# SOLAR_PO.net
KiCad netlist of a schematic drawn in Altium Designer
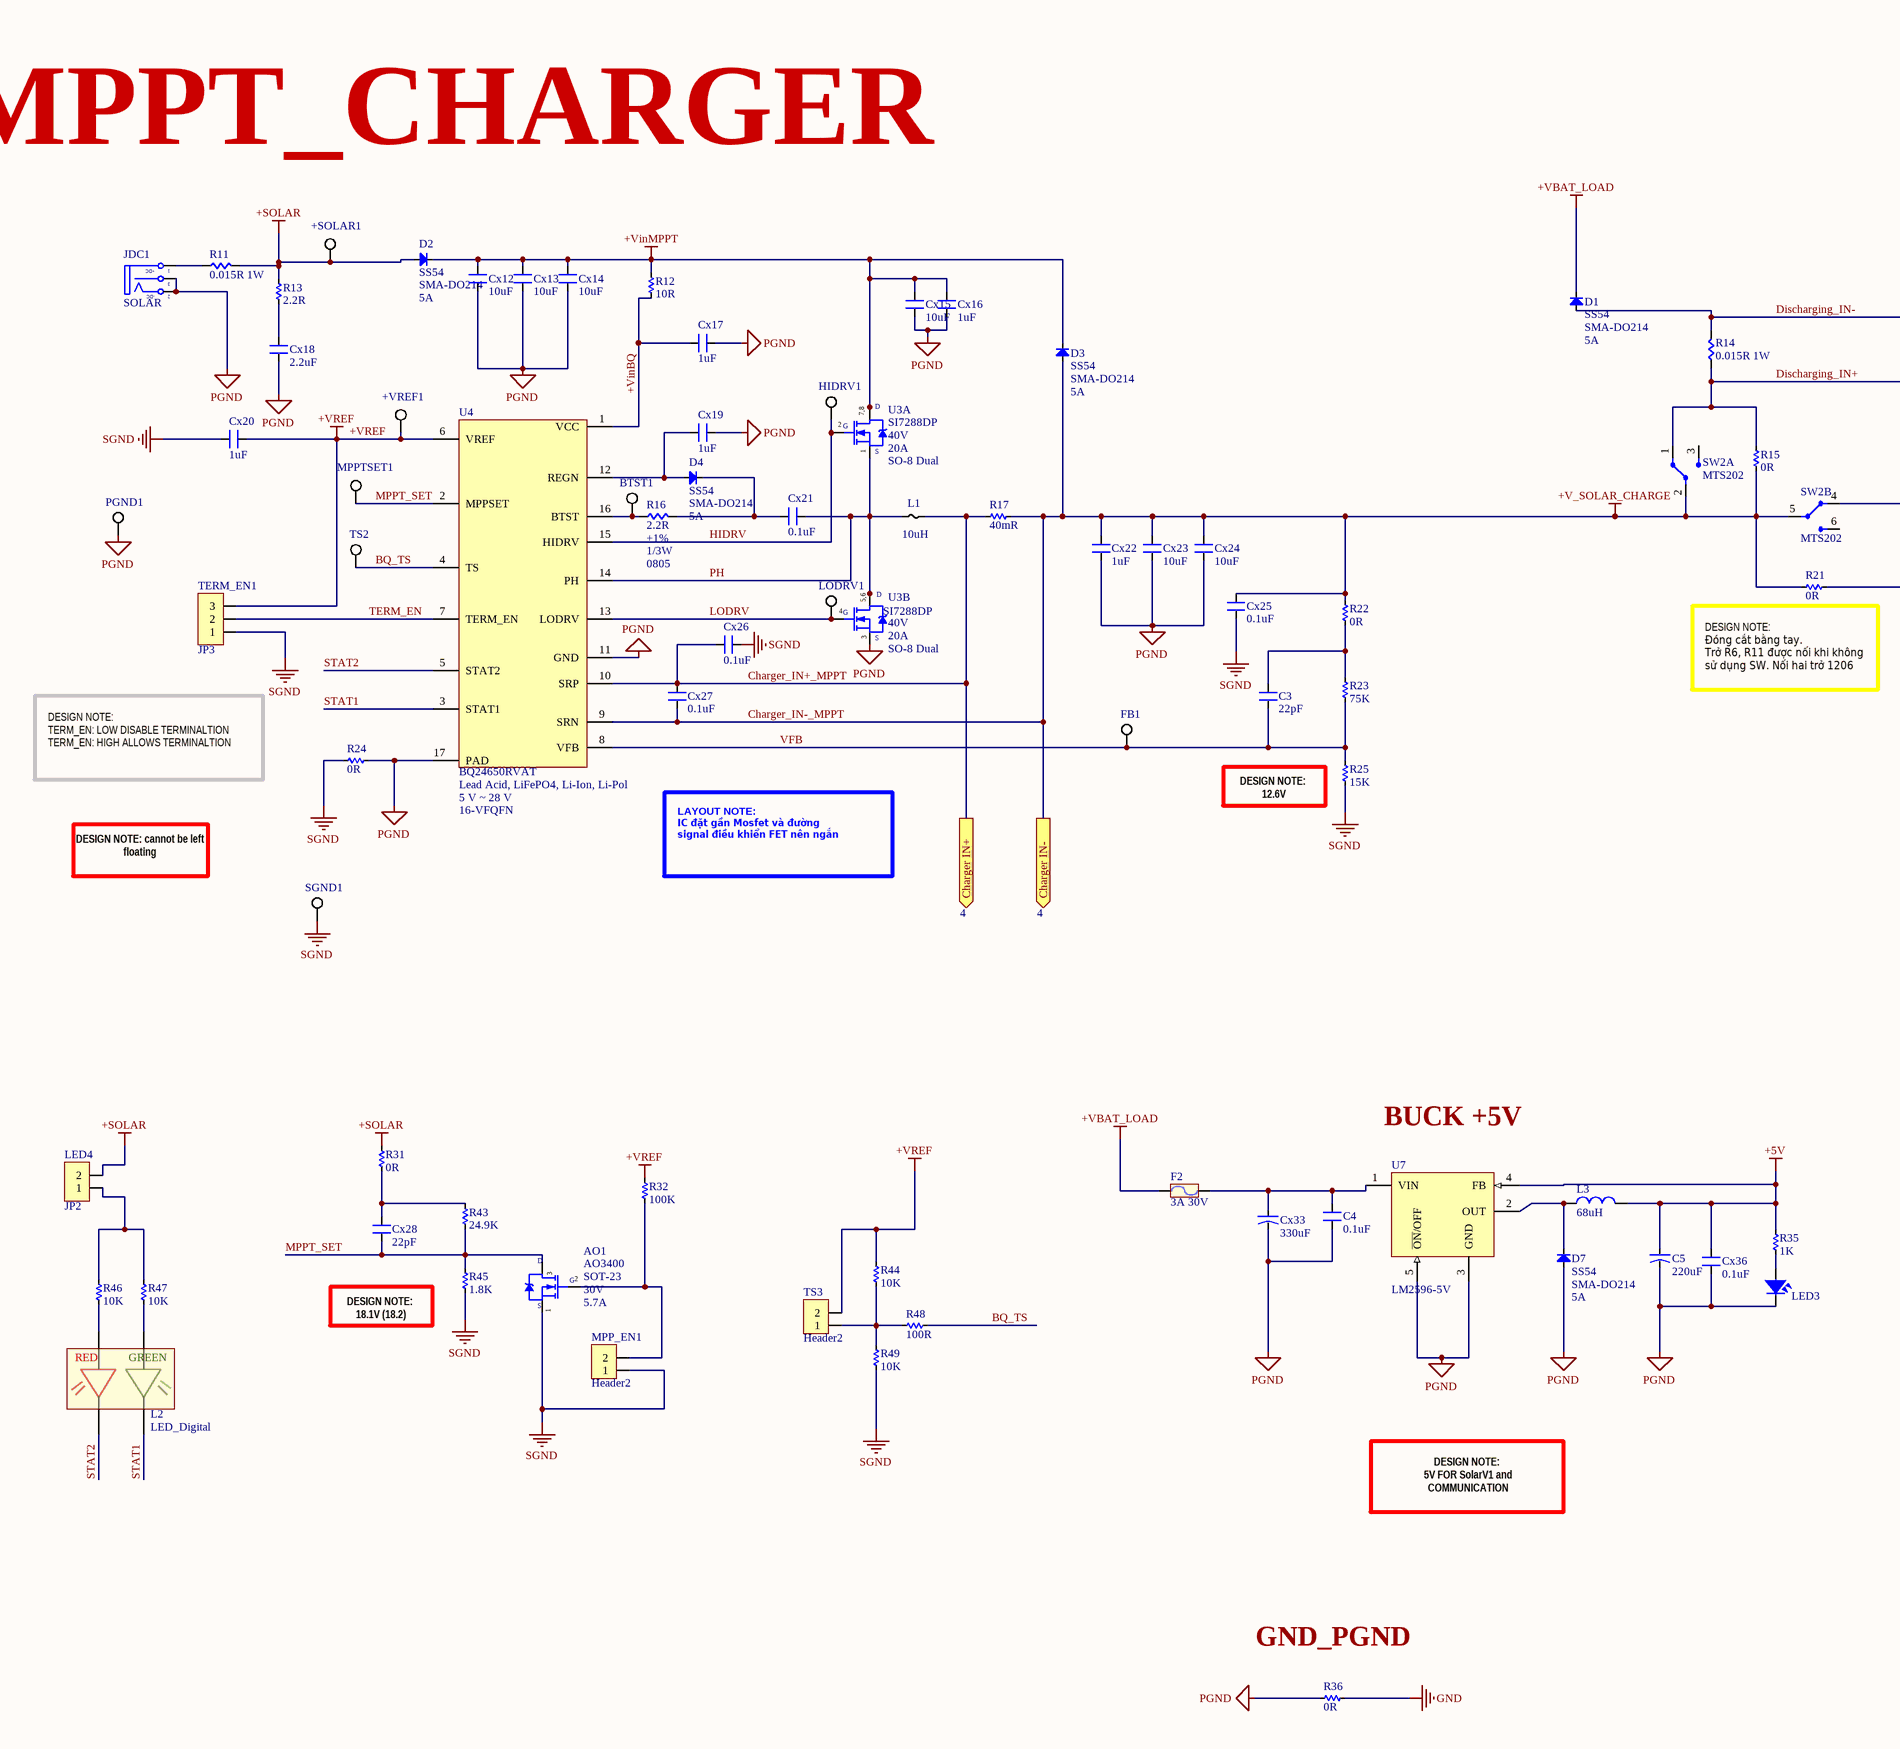
[diagram p0: SOLAR_PO.SchDoc, left]
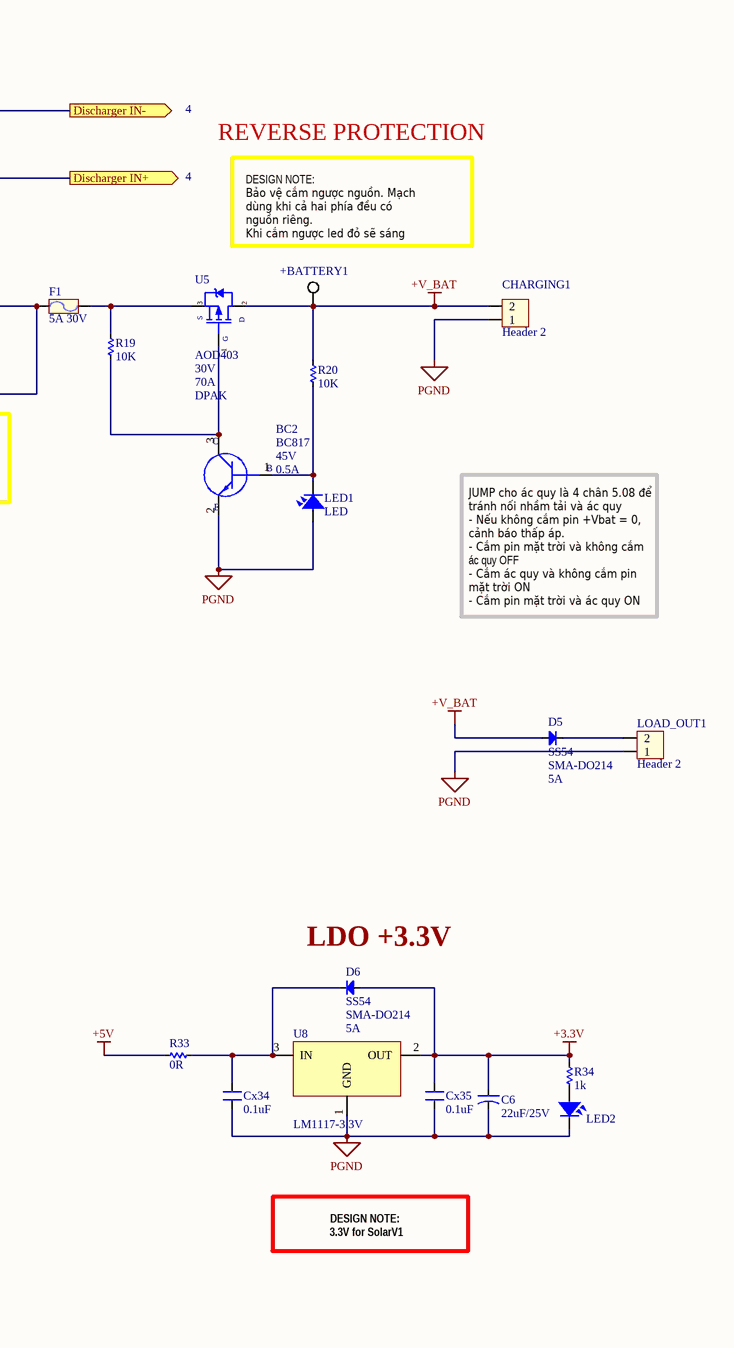
[diagram p1: SOLAR_PO.SchDoc, right]

(export (version "E")
  (design (tool "Eeschema 10.0.6"))
  (components
    (comp (ref "+BATTERY1")
      (value "TP 2x2mm")
      (footprint "TP 2x2mm")
      (libsource (lib "SolarV1") (part "TP 2x2mm"))
    )
    (comp (ref "+SOLAR1")
      (value "TP 2x2mm")
      (footprint "TP 2x2mm")
      (libsource (lib "SolarV1") (part "TP 2x2mm"))
    )
    (comp (ref "+VREF1")
      (value "TP 2x2mm")
      (footprint "TP 2x2mm")
      (libsource (lib "SolarV1") (part "TP 2x2mm"))
    )
    (comp (ref "AO1")
      (value "AO3400")
      (footprint "SOT23-231")
      (description "MOSFET N-CH 30V 5.7A SOT23")
      (fields
        (field (name "MANUFACTURER") "Alpha & Omega Semiconductor")
        (field (name "MANUFACTURER PART NUMBER") "AO3400A")
        (field (name "PACKAGE TYPE") "SOT-23")
        (field (name "DRAIN-SOURCE ON-VOLT") "30V")
        (field (name "CONTINUOUS DRAIN CURRENT") "5.7A")
      )
      (libsource (lib "SolarV1") (part "FET N-CH 4A 30V AO3400A"))
    )
    (comp (ref "BC2")
      (value "BC817")
      (footprint "SOT23-132")
      (description "BC817 Series 45 V 500 mA SMT NPN General Purpose Transistor - SOT-23 VN")
      (fields
        (field (name "MANUFACTURER") "Nexperia")
        (field (name "MANUFACTURER PART NUMBER") "BC817-25,215")
        (field (name "VOLTAGE") "45V")
        (field (name "CURRENT") "0.5A")
      )
      (libsource (lib "SolarV1") (part "TRAN 0.5A 45V BC817-25,215 SOT23 VN"))
    )
    (comp (ref "BTST1")
      (value "TP 2x2mm")
      (footprint "TP 2x2mm")
      (libsource (lib "SolarV1") (part "TP 2x2mm"))
    )
    (comp (ref "C3")
      (value "22pF")
      (footprint "SM-0805")
      (description "Cap Ceramic 22pF 50V C0G 10% Pad SMD 0805 125°C T/R")
      (libsource (lib "SolarV1") (part "CM"))
    )
    (comp (ref "C4")
      (value "0.1uF")
      (footprint "SM-0805")
      (description "Cap SMD")
      (libsource (lib "SolarV1") (part "CM"))
    )
    (comp (ref "C5")
      (value "220uF")
      (footprint "CAP-ALU-SMD-F")
      (description "Polarized Capacitor (Axial)")
      (fields (field (name "PUBLISHER") "Altium Limited"))
      (libsource (lib "SolarV1") (part "CN-ALU-SMD"))
    )
    (comp (ref "C6")
      (value "22uF/25V")
      (footprint "CAP-ALU-SMD-4.5x5x1.4")
      (description "Polarized Capacitor (Axial)")
      (fields (field (name "PUBLISHER") "Altium Limited"))
      (libsource (lib "SolarV1") (part "CN-ALU-SMD"))
    )
    (comp (ref "CHARGING1")
      (value "Header 2")
      (footprint "HED2T")
      (description "Header 2 (Green)")
      (libsource (lib "SolarV1") (part "Hed2"))
    )
    (comp (ref "Cx12") (value "10uF") (footprint "CN-SMD-0805") (libsource (lib "SolarV1") (part "CN")))
    (comp (ref "Cx13") (value "10uF") (footprint "CN-SMD-0805") (libsource (lib "SolarV1") (part "CN")))
    (comp (ref "Cx14") (value "10uF") (footprint "CN-SMD-0805") (libsource (lib "SolarV1") (part "CN")))
    (comp (ref "Cx15") (value "10uF") (footprint "CN-SMD-0805") (libsource (lib "SolarV1") (part "CN")))
    (comp (ref "Cx16") (value "1uF") (footprint "CN-SMD-0805") (libsource (lib "SolarV1") (part "CN")))
    (comp (ref "Cx17") (value "1uF") (footprint "CN-SMD-0805") (libsource (lib "SolarV1") (part "CN")))
    (comp (ref "Cx18") (value "2.2uF") (footprint "CN-SMD-0805") (libsource (lib "SolarV1") (part "CN")))
    (comp (ref "Cx19") (value "1uF") (footprint "CN-SMD-0805") (libsource (lib "SolarV1") (part "CN")))
    (comp (ref "Cx20") (value "1uF") (footprint "CN-SMD-0805") (libsource (lib "SolarV1") (part "CN")))
    (comp (ref "Cx21") (value "0.1uF") (footprint "CN-SMD-0805") (libsource (lib "SolarV1") (part "CN")))
    (comp (ref "Cx22") (value "1uF") (footprint "CN-SMD-0805") (libsource (lib "SolarV1") (part "CN")))
    (comp (ref "Cx23") (value "10uF") (footprint "CN-SMD-0805") (libsource (lib "SolarV1") (part "CN")))
    (comp (ref "Cx24") (value "10uF") (footprint "CN-SMD-0805") (libsource (lib "SolarV1") (part "CN")))
    (comp (ref "Cx25") (value "0.1uF") (footprint "CN-SMD-0805") (libsource (lib "SolarV1") (part "CN")))
    (comp (ref "Cx26") (value "0.1uF") (footprint "CN-SMD-0805") (libsource (lib "SolarV1") (part "CN")))
    (comp (ref "Cx27") (value "0.1uF") (footprint "CN-SMD-0805") (libsource (lib "SolarV1") (part "CN")))
    (comp (ref "Cx28") (value "22pF") (footprint "CN-SMD-0805") (libsource (lib "SolarV1") (part "CN")))
    (comp (ref "Cx33")
      (value "330uF")
      (footprint "CAP SMD ALU SIZE F")
      (description "Polarized Capacitor (Axial)")
      (fields (field (name "PUBLISHER") "Altium Limited"))
      (libsource (lib "SolarV1") (part "CN-ALU-SMD"))
    )
    (comp (ref "Cx34") (value "0.1uF") (footprint "CN-SMD-0805") (libsource (lib "SolarV1") (part "CN")))
    (comp (ref "Cx35") (value "0.1uF") (footprint "CN-SMD-0805") (libsource (lib "SolarV1") (part "CN")))
    (comp (ref "Cx36") (value "0.1uF") (footprint "CN-SMD-0805") (libsource (lib "SolarV1") (part "CN")))
    (comp (ref "D1")
      (value "SS54")
      (footprint "SMA (DO-214AC)")
      (description "SS54 SMA/DO-124AC 5A 40V Schottky Barrier (1N5824) VN")
      (fields (field (name "PACKAGE") "SMA-DO214") (field (name "CURRENT") "5A"))
      (libsource (lib "SolarV1") (part "DIODE 5A 40V SS54  Schottky Diode VN"))
    )
    (comp (ref "D2")
      (value "SS54")
      (footprint "SMA (DO-214AC)")
      (description "SS54 SMA/DO-124AC 5A 40V Schottky Barrier (1N5824) VN")
      (fields (field (name "PACKAGE") "SMA-DO214") (field (name "CURRENT") "5A"))
      (libsource (lib "SolarV1") (part "DIODE 5A 40V SS54  Schottky Diode VN"))
    )
    (comp (ref "D3")
      (value "SS54")
      (footprint "SMA (DO-214AC)")
      (description "SS54 SMA/DO-124AC 5A 40V Schottky Barrier (1N5824) VN")
      (fields (field (name "PACKAGE") "SMA-DO214") (field (name "CURRENT") "5A"))
      (libsource (lib "SolarV1") (part "DIODE 5A 40V SS54  Schottky Diode VN"))
    )
    (comp (ref "D4")
      (value "SS54")
      (footprint "SMA (DO-214AC)")
      (description "SS54 SMA/DO-124AC 5A 40V Schottky Barrier (1N5824) VN")
      (fields (field (name "PACKAGE") "SMA-DO214") (field (name "CURRENT") "5A"))
      (libsource (lib "SolarV1") (part "DIODE 5A 40V SS54  Schottky Diode VN"))
    )
    (comp (ref "D5")
      (value "SS54")
      (footprint "SMA (DO-214AC)")
      (description "SS54 SMA/DO-124AC 5A 40V Schottky Barrier (1N5824) VN")
      (fields (field (name "PACKAGE") "SMA-DO214") (field (name "CURRENT") "5A"))
      (libsource (lib "SolarV1") (part "DIODE 5A 40V SS54  Schottky Diode VN"))
    )
    (comp (ref "D6")
      (value "SS54")
      (footprint "SMA (DO-214AC)")
      (description "SS54 SMA/DO-124AC 5A 40V Schottky Barrier (1N5824) VN")
      (fields (field (name "PACKAGE") "SMA-DO214") (field (name "CURRENT") "5A"))
      (libsource (lib "SolarV1") (part "DIODE 5A 40V SS54  Schottky Diode VN"))
    )
    (comp (ref "D7")
      (value "SS54")
      (footprint "SMA (DO-214AC)")
      (description "SS54 SMA/DO-124AC 5A 40V Schottky Barrier (1N5824) VN")
      (fields (field (name "PACKAGE") "SMA-DO214") (field (name "CURRENT") "5A"))
      (libsource (lib "SolarV1") (part "DIODE 5A 40V SS54  Schottky Diode VN"))
    )
    (comp (ref "F1") (value "5A 30V") (footprint "CN4") (libsource (lib "SolarV1") (part "FUSR 4A 30V DIP")))
    (comp (ref "F2")
      (value "3A 30V")
      (footprint "CN2-G")
      (libsource (lib "SolarV1") (part "FUSE 4A 30V DIP"))
    )
    (comp (ref "FB1") (value "TP 2x2mm") (footprint "TP 2x2mm") (libsource (lib "SolarV1") (part "TP 2x2mm")))
    (comp (ref "HIDRV1")
      (value "TP 2x2mm")
      (footprint "TP 2x2mm")
      (libsource (lib "SolarV1") (part "TP 2x2mm"))
    )
    (comp (ref "JDC1")
      (value "SOLAR")
      (footprint "DC0")
      (description "Jac DC input")
      (libsource (lib "SolarV1") (part "DCIN"))
    )
    (comp (ref "L1")
      (value "10uH")
      (footprint "CDRH104R")
      (description "CDRH104,104R")
      (libsource (lib "SolarV1") (part "inductor"))
    )
    (comp (ref "L2")
      (value "LED_Digital")
      (footprint "LedDigital")
      (description "DBL2")
      (libsource (lib "SolarV1") (part "LED_Digital"))
    )
    (comp (ref "L3")
      (value "68uH")
      (footprint "INDUCTOR SMD 12x12X8.5mm")
      (description "FIXED IND 33UH 3A 64.8 MOHM SMD")
      (fields
        (field (name "MANUFACTURER") "Sumida")
        (field (name "MANUFACTURER PART NUMBER") "CDRH127NP-330MC")
      )
      (libsource (lib "SolarV1") (part "IND 33UH 3A CDRH127NP-330MC"))
    )
    (comp (ref "LED1")
      (value "LED")
      (footprint "LED-5 GRe")
      (description "LED Single colour Green and Red")
      (libsource (lib "SolarV1") (part "LED"))
    )
    (comp (ref "LED2") (value "LED") (footprint "LED-0805-Blue") (libsource (lib "SolarV1") (part "LED SMD")))
    (comp (ref "LED3") (value "LED") (footprint "LED-0805-Red") (libsource (lib "SolarV1") (part "LED SMD")))
    (comp (ref "LED4")
      (value "JP2")
      (footprint "JP2-CLOSED")
      (description "WR-PHD 2.54 mm Angled Socket Header")
      (fields
        (field (name "MANUFACTURER") "Würth Elektronik eiSos GmbH")
        (field (name "PARTNO") "613002143121")
        (field (name "CREATED BY") "Karrer Zheng")
      )
      (libsource (lib "SolarV1") (part "JP2"))
    )
    (comp (ref "LOAD_OUT1")
      (value "Header 2")
      (footprint "HED2T")
      (description "Header 2 (Green)")
      (libsource (lib "SolarV1") (part "Hed2"))
    )
    (comp (ref "LODRV1")
      (value "TP 2x2mm")
      (footprint "TP 2x2mm")
      (libsource (lib "SolarV1") (part "TP 2x2mm"))
    )
    (comp (ref "MPPTSET1")
      (value "TP 2x2mm")
      (footprint "TP 2x2mm")
      (libsource (lib "SolarV1") (part "TP 2x2mm"))
    )
    (comp (ref "MPP_EN1")
      (value "Header2")
      (footprint "JP2-D1T")
      (description "Header IDC, 2 x 1 Pin Vertical 2.54mm Pitch (Non-Boxed, Male)")
      (fields
        (field (name "MANUFACTURER") "Würth Elektronik eiSos GmbH")
        (field (name "PARTNO") "613002143121")
        (field (name "CREATED BY") "Karrer Zheng")
      )
      (libsource (lib "SolarV1") (part "Header2"))
    )
    (comp (ref "PGND1")
      (value "TP 2x2mm")
      (footprint "TP 2x2mm")
      (libsource (lib "SolarV1") (part "TP 2x2mm"))
    )
    (comp (ref "R11")
      (value "0.015R 1W")
      (footprint "RES-SMD-2512")
      (description "RES SMD 15 MOHM 1% 1W 2512")
      (fields
        (field (name "MANUFACTURER") "Vishay Dale")
        (field (name "MANUFACTURER PART NUMBER") "WSL2512R0150FEA")
      )
      (libsource (lib "SolarV1") (part "RES 0.015R 2512 1W 1%"))
    )
    (comp (ref "R12")
      (value "10R")
      (footprint "RES-SMD-0805")
      (description "0805")
      (fields
        (field (name "MANUFACTURER") "Generic Components")
        (field (name "PUBLISHER") "Altium Hobart Technology Centre")
      )
      (libsource (lib "SolarV1") (part "Res-SMD"))
    )
    (comp (ref "R13")
      (value "2.2R")
      (footprint "RES-SMD-2512")
      (description "Resistor")
      (fields
        (field (name "MANUFACTURER") "Generic Components")
        (field (name "PUBLISHER") "Altium Hobart Technology Centre")
      )
      (libsource (lib "SolarV1") (part "Res-SMD"))
    )
    (comp (ref "R14")
      (value "0.015R 1W")
      (footprint "RES-SMD-2512")
      (description "RES SMD 15 MOHM 1% 1W 2512")
      (fields
        (field (name "MANUFACTURER") "Vishay Dale")
        (field (name "MANUFACTURER PART NUMBER") "WSL2512R0150FEA")
      )
      (libsource (lib "SolarV1") (part "RES 0.015R 2512 1W 1%"))
    )
    (comp (ref "R15")
      (value "0R")
      (footprint "RES-SMD-1206")
      (description "Resistor")
      (fields
        (field (name "MANUFACTURER") "Generic Components")
        (field (name "PUBLISHER") "Altium Hobart Technology Centre")
      )
      (libsource (lib "SolarV1") (part "Res-SMD"))
    )
    (comp (ref "R16")
      (value "2.2R")
      (footprint "RES-SMD-0805")
      (description "RES SMD 2.2 OHM 1% 1/3W 0805 VN")
      (fields
        (field (name "MANUFACTURER") "Susumu")
        (field (name "MANUFACTURER PART NUMBER") "RL1220S-2R2-F")
        (field (name "TOLERANCE") "±1%")
        (field (name "POWER (WATTS)") "1/3W")
        (field (name "SUPPLIER DEVICE PACKAGE") "0805")
      )
      (libsource (lib "SolarV1") (part "RES 2.2R 1% 0805 RL1220S-2R2-F VN"))
    )
    (comp (ref "R17")
      (value "40mR")
      (footprint "RES-SMD-2512")
      (description "Resistor")
      (fields
        (field (name "MANUFACTURER") "Generic Components")
        (field (name "PUBLISHER") "Altium Hobart Technology Centre")
      )
      (libsource (lib "SolarV1") (part "Res-SMD"))
    )
    (comp (ref "R19")
      (value "10K")
      (footprint "RES-SMD-0805")
      (description "Resistor")
      (fields
        (field (name "MANUFACTURER") "Generic Components")
        (field (name "PUBLISHER") "Altium Hobart Technology Centre")
      )
      (libsource (lib "SolarV1") (part "Res-SMD"))
    )
    (comp (ref "R20")
      (value "10K")
      (footprint "RES-SMD-0805")
      (description "Resistor")
      (fields
        (field (name "MANUFACTURER") "Generic Components")
        (field (name "PUBLISHER") "Altium Hobart Technology Centre")
      )
      (libsource (lib "SolarV1") (part "Res-SMD"))
    )
    (comp (ref "R21")
      (value "0R")
      (footprint "RES-SMD-1206")
      (description "Resistor")
      (fields
        (field (name "MANUFACTURER") "Generic Components")
        (field (name "PUBLISHER") "Altium Hobart Technology Centre")
      )
      (libsource (lib "SolarV1") (part "Res-SMD"))
    )
    (comp (ref "R22")
      (value "0R")
      (footprint "RES-SMD-0805")
      (description "Resistor")
      (fields
        (field (name "MANUFACTURER") "Generic Components")
        (field (name "PUBLISHER") "Altium Hobart Technology Centre")
      )
      (libsource (lib "SolarV1") (part "Res-SMD"))
    )
    (comp (ref "R23")
      (value "75K")
      (footprint "RES-SMD-0805")
      (description "Resistor")
      (fields
        (field (name "MANUFACTURER") "Generic Components")
        (field (name "PUBLISHER") "Altium Hobart Technology Centre")
      )
      (libsource (lib "SolarV1") (part "Res-SMD"))
    )
    (comp (ref "R24")
      (value "0R")
      (footprint "RES-SMD-0805")
      (description "Resistor")
      (fields
        (field (name "MANUFACTURER") "Generic Components")
        (field (name "PUBLISHER") "Altium Hobart Technology Centre")
      )
      (libsource (lib "SolarV1") (part "Res-SMD"))
    )
    (comp (ref "R25")
      (value "15K")
      (footprint "RES-SMD-0805")
      (description "Resistor")
      (fields
        (field (name "MANUFACTURER") "Generic Components")
        (field (name "PUBLISHER") "Altium Hobart Technology Centre")
      )
      (libsource (lib "SolarV1") (part "Res-SMD"))
    )
    (comp (ref "R31")
      (value "0R")
      (footprint "RES-SMD-0805")
      (description "Resistor")
      (fields
        (field (name "MANUFACTURER") "Generic Components")
        (field (name "PUBLISHER") "Altium Hobart Technology Centre")
      )
      (libsource (lib "SolarV1") (part "Res-SMD"))
    )
    (comp (ref "R32")
      (value "100K")
      (footprint "RES-SMD-0805")
      (description "Resistor")
      (fields
        (field (name "MANUFACTURER") "Generic Components")
        (field (name "PUBLISHER") "Altium Hobart Technology Centre")
      )
      (libsource (lib "SolarV1") (part "Res-SMD"))
    )
    (comp (ref "R33")
      (value "0R")
      (footprint "RES-SMD-0805")
      (description "Resistor")
      (fields
        (field (name "MANUFACTURER") "Generic Components")
        (field (name "PUBLISHER") "Altium Hobart Technology Centre")
      )
      (libsource (lib "SolarV1") (part "Res-SMD"))
    )
    (comp (ref "R34")
      (value "1k")
      (footprint "RES-SMD-0805")
      (description "Resistor")
      (fields
        (field (name "MANUFACTURER") "Generic Components")
        (field (name "PUBLISHER") "Altium Hobart Technology Centre")
      )
      (libsource (lib "SolarV1") (part "Res-SMD"))
    )
    (comp (ref "R35")
      (value "1K")
      (footprint "RES-SMD-0805")
      (description "Resistor")
      (fields
        (field (name "MANUFACTURER") "Generic Components")
        (field (name "PUBLISHER") "Altium Hobart Technology Centre")
      )
      (libsource (lib "SolarV1") (part "Res-SMD"))
    )
    (comp (ref "R36")
      (value "0R")
      (footprint "RES-SMD-0805")
      (description "Resistor")
      (fields
        (field (name "MANUFACTURER") "Generic Components")
        (field (name "PUBLISHER") "Altium Hobart Technology Centre")
      )
      (libsource (lib "SolarV1") (part "Res-SMD"))
    )
    (comp (ref "R43")
      (value "24.9K")
      (footprint "RES-SMD-0805")
      (description "Resistor")
      (fields
        (field (name "MANUFACTURER") "Generic Components")
        (field (name "PUBLISHER") "Altium Hobart Technology Centre")
      )
      (libsource (lib "SolarV1") (part "Res-SMD"))
    )
    (comp (ref "R44")
      (value "10K")
      (footprint "RES-SMD-0805")
      (description "Resistor")
      (fields
        (field (name "MANUFACTURER") "Generic Components")
        (field (name "PUBLISHER") "Altium Hobart Technology Centre")
      )
      (libsource (lib "SolarV1") (part "Res-SMD"))
    )
    (comp (ref "R45")
      (value "1.8K")
      (footprint "RES-SMD-0805")
      (description "Resistor")
      (fields
        (field (name "MANUFACTURER") "Generic Components")
        (field (name "PUBLISHER") "Altium Hobart Technology Centre")
      )
      (libsource (lib "SolarV1") (part "Res-SMD"))
    )
    (comp (ref "R46")
      (value "10K")
      (footprint "RES-SMD-0805")
      (description "Resistor")
      (fields
        (field (name "MANUFACTURER") "Generic Components")
        (field (name "PUBLISHER") "Altium Hobart Technology Centre")
      )
      (libsource (lib "SolarV1") (part "Res-SMD"))
    )
    (comp (ref "R47")
      (value "10K")
      (footprint "RES-SMD-0805")
      (description "Resistor")
      (fields
        (field (name "MANUFACTURER") "Generic Components")
        (field (name "PUBLISHER") "Altium Hobart Technology Centre")
      )
      (libsource (lib "SolarV1") (part "Res-SMD"))
    )
    (comp (ref "R48")
      (value "100R")
      (footprint "RES-SMD-0805")
      (description "Resistor")
      (fields
        (field (name "MANUFACTURER") "Generic Components")
        (field (name "PUBLISHER") "Altium Hobart Technology Centre")
      )
      (libsource (lib "SolarV1") (part "Res-SMD"))
    )
    (comp (ref "R49")
      (value "10K")
      (footprint "RES-SMD-0805")
      (description "Resistor")
      (fields
        (field (name "MANUFACTURER") "Generic Components")
        (field (name "PUBLISHER") "Altium Hobart Technology Centre")
      )
      (libsource (lib "SolarV1") (part "Res-SMD"))
    )
    (comp (ref "SGND1")
      (value "TP 2x2mm")
      (footprint "TP 2x2mm")
      (libsource (lib "SolarV1") (part "TP 2x2mm"))
    )
    (comp (ref "SW2") (value "MTS202") (footprint "MTS-20X") (libsource (lib "") (part "SW MTS202 ON-ON_1")))
    (comp (ref "TERM_EN1")
      (value "JP3")
      (footprint "JP3-D1T")
      (description "WR-PHD 2.54 mm Angled Socket Header")
      (fields
        (field (name "MANUFACTURER") "Würth Elektronik eiSos GmbH")
        (field (name "PARTNO") "613003143121")
        (field (name "CREATED BY") "Karrer Zheng")
      )
      (libsource (lib "SolarV1") (part "JP3"))
    )
    (comp (ref "TS2") (value "TP 2x2mm") (footprint "TP 2x2mm") (libsource (lib "SolarV1") (part "TP 2x2mm")))
    (comp (ref "TS3")
      (value "Header2")
      (footprint "JP2-D1T")
      (description "Header IDC, 2 x 1 Pin Vertical 2.54mm Pitch (Non-Boxed, Male)")
      (fields
        (field (name "MANUFACTURER") "Würth Elektronik eiSos GmbH")
        (field (name "PARTNO") "613002143121")
        (field (name "CREATED BY") "Karrer Zheng")
      )
      (libsource (lib "SolarV1") (part "Header2"))
    )
    (comp (ref "U3")
      (value "SI7288DP")
      (footprint "SO-8 PowerPAK")
      (description "MOSFET 2N-CH 40V 20A PPAK SO-8")
      (fields
        (field (name "MANUFACTURER") "Vishay Siliconix")
        (field (name "MANUFACTURER PART NUMBER") "SI7288DP-T1-GE3")
        (field (name "DRAIN TO SOURCE VOLTAGE (VDSS)") "40V")
        (field (name "CURRENT - CONTINUOUS DRAIN (ID) @ 25°C") "20A")
        (field (name "PACKAGE / CASE") "SO-8 Dual")
      )
      (libsource (lib "SolarV1") (part "FET SI7288DP-T1-GE3"))
    )
    (comp (ref "U4")
      (value "BQ24650RVAT")
      (footprint "VFQFN-16-EP")
      (description "TEXAS INSTRUMENTS         BQ24650RVAT            IC, BATT CHARGER, LI-ION, 10A, VQFN-16")
      (fields
        (field (name "MANUFACTURER") "Texas Instruments")
        (field (name "BATTERY CHEMISTRY") "Lead Acid, LiFePO4, Li-Ion, Li-Pol")
        (field (name "VOLTAGE - SUPPLY") "5 V ~ 28 V")
        (field (name "PACKAGE / CASE") "16-VFQFN")
      )
      (libsource (lib "SolarV1") (part "BQ24650RVAT"))
    )
    (comp (ref "U5")
      (value "AOD403")
      (footprint "TO-252 DPAK")
      (description "Trans MOSFET P-CH 30V 70A 3-Pin(2+Tab) DPAK VN")
      (fields
        (field (name "MANUFACTURER") "Alpha & Omega Semiconductor")
        (field (name "DRAIN-SOURCE ON-VOLT") "30V")
        (field (name "CONTINUOUS DRAIN CURRENT") "70A")
        (field (name "PACKAGE TYPE") "DPAK")
      )
      (libsource (lib "SolarV1") (part "FET P-CH 70A 40V AOD403 VN"))
    )
    (comp (ref "U7")
      (value "LM2596-5V")
      (footprint "TO263")
      (description "IC REG BUCK 5V 3A TO263-5")
      (fields
        (field (name "MANUFACTURER") "Texas Instruments")
        (field (name "MANUFACTURER PART NUMBER") "LM2596SX-5.0/NOPB")
      )
      (libsource (lib "SolarV1") (part "BUCK 5V LM2596SX-5.0/NOPB"))
    )
    (comp (ref "U8")
      (value "LM1117-3.3V")
      (footprint "SOT223")
      (description "800mA Low-Dropout Linear Regulator")
      (fields (field (name "CREATOR") "Nguyen Ba Bien"))
      (libsource (lib "SolarV1") (part "LM1117"))
    )
  )
  (nets
    (net (code "1") (name "+3.3V") (class "Default")
      (node (ref "C6") (pin "1") (pinfunction "1_1") (pintype "passive"))
      (node (ref "Cx35") (pin "2") (pinfunction "2_2") (pintype "passive"))
      (node (ref "D6") (pin "1") (pinfunction "A_1") (pintype "passive"))
      (node (ref "R34") (pin "1") (pinfunction "1_1") (pintype "passive"))
      (node (ref "U8") (pin "2") (pinfunction "OUT_2") (pintype "passive"))
    )
    (net (code "2") (name "+5V") (class "Default")
      (node (ref "C5") (pin "1") (pinfunction "1_1") (pintype "passive"))
      (node (ref "Cx36") (pin "2") (pinfunction "2_2") (pintype "passive"))
      (node (ref "L3") (pin "2") (pinfunction "2_2") (pintype "passive"))
      (node (ref "R33") (pin "2") (pinfunction "2_2") (pintype "passive"))
      (node (ref "R35") (pin "1") (pinfunction "1_1") (pintype "passive"))
      (node (ref "U7") (pin "4") (pinfunction "FB_4") (pintype "input"))
    )
    (net (code "3") (name "+SOLAR") (class "Default")
      (node (ref "+SOLAR1") (pin "3") (pinfunction "3_3") (pintype "passive"))
      (node (ref "D2") (pin "1") (pinfunction "A_1") (pintype "passive"))
      (node (ref "LED4") (pin "2") (pinfunction "2_2") (pintype "passive"))
      (node (ref "R11") (pin "2") (pinfunction "2_2") (pintype "passive"))
      (node (ref "R13") (pin "1") (pinfunction "1_1") (pintype "passive"))
      (node (ref "R31") (pin "1") (pinfunction "1_1") (pintype "passive"))
    )
    (net (code "4") (name "+VBAT_LOAD") (class "Default")
      (node (ref "D1") (pin "2") (pinfunction "K_2") (pintype "passive"))
      (node (ref "F2") (pin "1") (pinfunction "1_1") (pintype "passive"))
    )
    (net (code "5") (name "+VREF") (class "Default")
      (node (ref "+VREF1") (pin "3") (pinfunction "3_3") (pintype "passive"))
      (node (ref "Cx20") (pin "1") (pinfunction "1_1") (pintype "passive"))
      (node (ref "R32") (pin "1") (pinfunction "1_1") (pintype "passive"))
      (node (ref "R44") (pin "1") (pinfunction "1_1") (pintype "passive"))
      (node (ref "TERM_EN1") (pin "3") (pinfunction "3_3") (pintype "passive"))
      (node (ref "TS3") (pin "2") (pinfunction "2_2") (pintype "passive"))
      (node (ref "U4") (pin "6") (pinfunction "VREF_6") (pintype "passive"))
    )
    (net (code "6") (name "+V_BAT") (class "Default")
      (node (ref "+BATTERY1") (pin "3") (pinfunction "3_3") (pintype "passive"))
      (node (ref "CHARGING1") (pin "2") (pinfunction "2_2") (pintype "passive"))
      (node (ref "D5") (pin "1") (pinfunction "A_1") (pintype "passive"))
      (node (ref "R20") (pin "2") (pinfunction "2_2") (pintype "passive"))
      (node (ref "U5") (pin "2") (pinfunction "D_2") (pintype "passive"))
    )
    (net (code "7") (name "+V_SOLAR_CHARGE") (class "Default")
      (node (ref "Cx22") (pin "1") (pinfunction "1_1") (pintype "passive"))
      (node (ref "Cx23") (pin "1") (pinfunction "1_1") (pintype "passive"))
      (node (ref "Cx24") (pin "2") (pinfunction "2_2") (pintype "passive"))
      (node (ref "Cx25") (pin "1") (pinfunction "1_1") (pintype "passive"))
      (node (ref "Cx27") (pin "2") (pinfunction "2_2") (pintype "passive"))
      (node (ref "D3") (pin "1") (pinfunction "A_1") (pintype "passive"))
      (node (ref "R15") (pin "1") (pinfunction "1_1") (pintype "passive"))
      (node (ref "R17") (pin "1") (pinfunction "1_1") (pintype "passive"))
      (node (ref "R21") (pin "1") (pinfunction "1_1") (pintype "passive"))
      (node (ref "R22") (pin "1") (pinfunction "1_1") (pintype "passive"))
      (node (ref "SW2") (pin "2") (pintype "passive"))
      (node (ref "SW2") (pin "5") (pintype "passive"))
      (node (ref "U4") (pin "9") (pinfunction "SRN_9") (pintype "passive"))
    )
    (net (code "8") (name "+VinMPPT") (class "Default")
      (node (ref "Cx12") (pin "2") (pinfunction "2_2") (pintype "passive"))
      (node (ref "Cx13") (pin "2") (pinfunction "2_2") (pintype "passive"))
      (node (ref "Cx14") (pin "2") (pinfunction "2_2") (pintype "passive"))
      (node (ref "Cx15") (pin "2") (pinfunction "2_2") (pintype "passive"))
      (node (ref "Cx16") (pin "1") (pinfunction "1_1") (pintype "passive"))
      (node (ref "D2") (pin "2") (pinfunction "K_2") (pintype "passive"))
      (node (ref "D3") (pin "2") (pinfunction "K_2") (pintype "passive"))
      (node (ref "R12") (pin "1") (pinfunction "1_1") (pintype "passive"))
      (node (ref "U3") (pin "7") (pinfunction "D_7") (pintype "passive"))
      (node (ref "U3") (pin "8") (pinfunction "D_8") (pintype "passive"))
    )
    (net (code "9") (name "/+VinBQ") (class "Default")
      (node (ref "Cx17") (pin "2") (pinfunction "2_2") (pintype "passive"))
      (node (ref "R12") (pin "2") (pinfunction "2_2") (pintype "passive"))
      (node (ref "U4") (pin "1") (pinfunction "VCC_1") (pintype "passive"))
    )
    (net (code "10") (name "/BQ_TS") (class "Default")
      (node (ref "R48") (pin "2") (pinfunction "2_2") (pintype "passive"))
      (node (ref "TS2") (pin "3") (pinfunction "3_3") (pintype "passive"))
      (node (ref "U4") (pin "4") (pinfunction "TS_4") (pintype "passive"))
    )
    (net (code "11") (name "/Charger_IN+_MPPT") (class "Default")
      (node (ref "Cx26") (pin "2") (pinfunction "2_2") (pintype "passive"))
      (node (ref "Cx27") (pin "1") (pinfunction "1_1") (pintype "passive"))
      (node (ref "L1") (pin "2") (pinfunction "2_2") (pintype "passive"))
      (node (ref "R17") (pin "2") (pinfunction "2_2") (pintype "passive"))
      (node (ref "U4") (pin "10") (pinfunction "SRP_10") (pintype "passive"))
    )
    (net (code "12") (name "/Discharging_IN+") (class "Default")
      (node (ref "R14") (pin "1") (pinfunction "1_1") (pintype "passive"))
      (node (ref "R15") (pin "2") (pinfunction "2_2") (pintype "passive"))
      (node (ref "SW2") (pin "1") (pintype "passive"))
    )
    (net (code "13") (name "/Discharging_IN-") (class "Default")
      (node (ref "D1") (pin "1") (pinfunction "A_1") (pintype "passive"))
      (node (ref "R14") (pin "2") (pinfunction "2_2") (pintype "passive"))
    )
    (net (code "14") (name "/HIDRV") (class "Default")
      (node (ref "HIDRV1") (pin "3") (pinfunction "3_3") (pintype "passive"))
      (node (ref "U3") (pin "2") (pinfunction "G_2") (pintype "passive"))
      (node (ref "U4") (pin "15") (pinfunction "HIDRV_15") (pintype "passive"))
    )
    (net (code "15") (name "/LODRV") (class "Default")
      (node (ref "LODRV1") (pin "3") (pinfunction "3_3") (pintype "passive"))
      (node (ref "U3") (pin "4") (pinfunction "G_4") (pintype "passive"))
      (node (ref "U4") (pin "13") (pinfunction "LODRV_13") (pintype "passive"))
    )
    (net (code "16") (name "/MPPT_SET") (class "Default")
      (node (ref "AO1") (pin "3") (pinfunction "D_3") (pintype "passive"))
      (node (ref "Cx28") (pin "2") (pinfunction "2_2") (pintype "passive"))
      (node (ref "MPPTSET1") (pin "3") (pinfunction "3_3") (pintype "passive"))
      (node (ref "R43") (pin "2") (pinfunction "2_2") (pintype "passive"))
      (node (ref "R45") (pin "1") (pinfunction "1_1") (pintype "passive"))
      (node (ref "U4") (pin "2") (pinfunction "MPPSET_2") (pintype "passive"))
    )
    (net (code "17") (name "/PH") (class "Default")
      (node (ref "Cx21") (pin "1") (pinfunction "1_1") (pintype "passive"))
      (node (ref "L1") (pin "1") (pinfunction "1_1") (pintype "passive"))
      (node (ref "U3") (pin "1") (pinfunction "S_1") (pintype "passive"))
      (node (ref "U3") (pin "5") (pinfunction "D_5") (pintype "passive"))
      (node (ref "U3") (pin "6") (pinfunction "D_6") (pintype "passive"))
      (node (ref "U4") (pin "14") (pinfunction "PH_14") (pintype "passive"))
    )
    (net (code "18") (name "/STAT1") (class "Default")
      (node (ref "L2") (pin "4") (pinfunction "4_4") (pintype "passive"))
      (node (ref "U4") (pin "3") (pinfunction "STAT1_3") (pintype "passive"))
    )
    (net (code "19") (name "/STAT2") (class "Default")
      (node (ref "L2") (pin "2") (pinfunction "2_2") (pintype "passive"))
      (node (ref "U4") (pin "5") (pinfunction "STAT2_5") (pintype "passive"))
    )
    (net (code "20") (name "/TERM_EN") (class "Default")
      (node (ref "TERM_EN1") (pin "2") (pinfunction "2_2") (pintype "passive"))
      (node (ref "U4") (pin "7") (pinfunction "TERM_EN_7") (pintype "passive"))
    )
    (net (code "21") (name "/VFB") (class "Default")
      (node (ref "C3") (pin "1") (pinfunction "1_1") (pintype "passive"))
      (node (ref "FB1") (pin "3") (pinfunction "3_3") (pintype "passive"))
      (node (ref "R23") (pin "2") (pinfunction "2_2") (pintype "passive"))
      (node (ref "R25") (pin "1") (pinfunction "1_1") (pintype "passive"))
      (node (ref "U4") (pin "8") (pinfunction "VFB_8") (pintype "passive"))
    )
    (net (code "22") (name "GND") (class "Default")
      (node (ref "R36") (pin "1") (pinfunction "1_1") (pintype "passive"))
    )
    (net (code "23") (name "Net-(AO1-G)") (class "Default")
      (node (ref "AO1") (pin "2") (pinfunction "G_2") (pintype "passive"))
      (node (ref "MPP_EN1") (pin "2") (pinfunction "2_2") (pintype "passive"))
      (node (ref "R32") (pin "2") (pinfunction "2_2") (pintype "passive"))
    )
    (net (code "24") (name "Net-(BC2-B)") (class "Default")
      (node (ref "BC2") (pin "1") (pinfunction "B_1") (pintype "passive"))
      (node (ref "LED1") (pin "2") (pinfunction "2_2") (pintype "passive"))
      (node (ref "R20") (pin "1") (pinfunction "1_1") (pintype "passive"))
    )
    (net (code "25") (name "Net-(BC2-C)") (class "Default")
      (node (ref "BC2") (pin "3") (pinfunction "C_3") (pintype "passive"))
      (node (ref "R19") (pin "1") (pinfunction "1_1") (pintype "passive"))
      (node (ref "U5") (pin "1") (pinfunction "G_1") (pintype "passive"))
    )
    (net (code "26") (name "Net-(C3-Pad2)") (class "Default")
      (node (ref "C3") (pin "2") (pinfunction "2_2") (pintype "passive"))
      (node (ref "R22") (pin "2") (pinfunction "2_2") (pintype "passive"))
      (node (ref "R23") (pin "1") (pinfunction "1_1") (pintype "passive"))
    )
    (net (code "27") (name "Net-(Cx18-Pad2)") (class "Default")
      (node (ref "Cx18") (pin "2") (pinfunction "2_2") (pintype "passive"))
      (node (ref "R13") (pin "2") (pinfunction "2_2") (pintype "passive"))
    )
    (net (code "28") (name "Net-(Cx28-Pad1)") (class "Default")
      (node (ref "Cx28") (pin "1") (pinfunction "1_1") (pintype "passive"))
      (node (ref "R31") (pin "2") (pinfunction "2_2") (pintype "passive"))
      (node (ref "R43") (pin "1") (pinfunction "1_1") (pintype "passive"))
    )
    (net (code "29") (name "Net-(D4-A)") (class "Default")
      (node (ref "Cx19") (pin "2") (pinfunction "2_2") (pintype "passive"))
      (node (ref "D4") (pin "1") (pinfunction "A_1") (pintype "passive"))
      (node (ref "U4") (pin "12") (pinfunction "REGN_12") (pintype "passive"))
    )
    (net (code "30") (name "Net-(D4-K)") (class "Default")
      (node (ref "Cx21") (pin "2") (pinfunction "2_2") (pintype "passive"))
      (node (ref "D4") (pin "2") (pinfunction "K_2") (pintype "passive"))
      (node (ref "R16") (pin "2") (pinfunction "2_2") (pintype "passive"))
    )
    (net (code "31") (name "Net-(D5-K)") (class "Default")
      (node (ref "D5") (pin "2") (pinfunction "K_2") (pintype "passive"))
      (node (ref "LOAD_OUT1") (pin "2") (pinfunction "2_2") (pintype "passive"))
    )
    (net (code "32") (name "Net-(D6-K)") (class "Default")
      (node (ref "Cx34") (pin "2") (pinfunction "2_2") (pintype "passive"))
      (node (ref "D6") (pin "2") (pinfunction "K_2") (pintype "passive"))
      (node (ref "R33") (pin "1") (pinfunction "1_1") (pintype "passive"))
      (node (ref "U8") (pin "3") (pinfunction "IN_3") (pintype "passive"))
    )
    (net (code "33") (name "Net-(D7-K)") (class "Default")
      (node (ref "D7") (pin "2") (pinfunction "K_2") (pintype "passive"))
      (node (ref "L3") (pin "1") (pinfunction "1_1") (pintype "passive"))
      (node (ref "U7") (pin "2") (pinfunction "OUT_2") (pintype "power_in"))
    )
    (net (code "34") (name "Net-(F1-Pad1)") (class "Default")
      (node (ref "F1") (pin "1") (pinfunction "1_1") (pintype "passive"))
      (node (ref "R21") (pin "2") (pinfunction "2_2") (pintype "passive"))
      (node (ref "SW2") (pin "4") (pintype "passive"))
    )
    (net (code "35") (name "Net-(JDC1-T)") (class "Default")
      (node (ref "JDC1") (pin "1") (pinfunction "T_1") (pintype "passive"))
      (node (ref "R11") (pin "1") (pinfunction "1_1") (pintype "passive"))
    )
    (net (code "36") (name "Net-(L2-Pad1)") (class "Default")
      (node (ref "L2") (pin "1") (pinfunction "1_1") (pintype "passive"))
      (node (ref "R46") (pin "2") (pinfunction "2_2") (pintype "passive"))
    )
    (net (code "37") (name "Net-(L2-Pad3)") (class "Default")
      (node (ref "L2") (pin "3") (pinfunction "3_3") (pintype "passive"))
      (node (ref "R47") (pin "2") (pinfunction "2_2") (pintype "passive"))
    )
    (net (code "38") (name "Net-(LED2-Pad1)") (class "Default")
      (node (ref "LED2") (pin "1") (pinfunction "1_1") (pintype "passive"))
      (node (ref "R34") (pin "2") (pinfunction "2_2") (pintype "passive"))
    )
    (net (code "39") (name "Net-(LED3-Pad1)") (class "Default")
      (node (ref "LED3") (pin "1") (pinfunction "1_1") (pintype "passive"))
      (node (ref "R35") (pin "2") (pinfunction "2_2") (pintype "passive"))
    )
    (net (code "40") (name "Net-(LED4-Pad1)") (class "Default")
      (node (ref "LED4") (pin "1") (pinfunction "1_1") (pintype "passive"))
      (node (ref "R46") (pin "1") (pinfunction "1_1") (pintype "passive"))
      (node (ref "R47") (pin "1") (pinfunction "1_1") (pintype "passive"))
    )
    (net (code "41") (name "Net-(R44-Pad2)") (class "Default")
      (node (ref "R44") (pin "2") (pinfunction "2_2") (pintype "passive"))
      (node (ref "R48") (pin "1") (pinfunction "1_1") (pintype "passive"))
      (node (ref "R49") (pin "1") (pinfunction "1_1") (pintype "passive"))
      (node (ref "TS3") (pin "1") (pinfunction "1_1") (pintype "passive"))
    )
    (net (code "42") (name "Net-(U4-BTST)") (class "Default")
      (node (ref "BTST1") (pin "3") (pinfunction "3_3") (pintype "passive"))
      (node (ref "R16") (pin "1") (pinfunction "1_1") (pintype "passive"))
      (node (ref "U4") (pin "16") (pinfunction "BTST_16") (pintype "passive"))
    )
    (net (code "43") (name "Net-(U5-S)") (class "Default")
      (node (ref "F1") (pin "2") (pinfunction "2_2") (pintype "passive"))
      (node (ref "R19") (pin "2") (pinfunction "2_2") (pintype "passive"))
      (node (ref "U5") (pin "3") (pinfunction "S_3") (pintype "passive"))
    )
    (net (code "44") (name "Net-(U7-VIN)") (class "Default")
      (node (ref "C4") (pin "2") (pinfunction "2_2") (pintype "passive"))
      (node (ref "Cx33") (pin "1") (pinfunction "1_1") (pintype "passive"))
      (node (ref "F2") (pin "2") (pinfunction "2_2") (pintype "passive"))
      (node (ref "U7") (pin "1") (pinfunction "VIN_1") (pintype "power_in"))
    )
    (net (code "45") (name "PGND") (class "Default")
      (node (ref "BC2") (pin "2") (pinfunction "E_2") (pintype "passive"))
      (node (ref "C4") (pin "1") (pinfunction "1_1") (pintype "passive"))
      (node (ref "C5") (pin "2") (pinfunction "2_2") (pintype "passive"))
      (node (ref "C6") (pin "2") (pinfunction "2_2") (pintype "passive"))
      (node (ref "CHARGING1") (pin "1") (pinfunction "1_1") (pintype "passive"))
      (node (ref "Cx12") (pin "1") (pinfunction "1_1") (pintype "passive"))
      (node (ref "Cx13") (pin "1") (pinfunction "1_1") (pintype "passive"))
      (node (ref "Cx14") (pin "1") (pinfunction "1_1") (pintype "passive"))
      (node (ref "Cx15") (pin "1") (pinfunction "1_1") (pintype "passive"))
      (node (ref "Cx16") (pin "2") (pinfunction "2_2") (pintype "passive"))
      (node (ref "Cx17") (pin "1") (pinfunction "1_1") (pintype "passive"))
      (node (ref "Cx18") (pin "1") (pinfunction "1_1") (pintype "passive"))
      (node (ref "Cx19") (pin "1") (pinfunction "1_1") (pintype "passive"))
      (node (ref "Cx22") (pin "2") (pinfunction "2_2") (pintype "passive"))
      (node (ref "Cx23") (pin "2") (pinfunction "2_2") (pintype "passive"))
      (node (ref "Cx24") (pin "1") (pinfunction "1_1") (pintype "passive"))
      (node (ref "Cx33") (pin "2") (pinfunction "2_2") (pintype "passive"))
      (node (ref "Cx34") (pin "1") (pinfunction "1_1") (pintype "passive"))
      (node (ref "Cx35") (pin "1") (pinfunction "1_1") (pintype "passive"))
      (node (ref "Cx36") (pin "1") (pinfunction "1_1") (pintype "passive"))
      (node (ref "D7") (pin "1") (pinfunction "A_1") (pintype "passive"))
      (node (ref "JDC1") (pin "2") (pinfunction "TN_2") (pintype "passive"))
      (node (ref "JDC1") (pin "3") (pinfunction "S_3") (pintype "power_in"))
      (node (ref "LED1") (pin "1") (pinfunction "1_1") (pintype "passive"))
      (node (ref "LED2") (pin "2") (pinfunction "2_2") (pintype "passive"))
      (node (ref "LED3") (pin "2") (pinfunction "2_2") (pintype "passive"))
      (node (ref "LOAD_OUT1") (pin "1") (pinfunction "1_1") (pintype "passive"))
      (node (ref "PGND1") (pin "3") (pinfunction "3_3") (pintype "passive"))
      (node (ref "R24") (pin "1") (pinfunction "1_1") (pintype "passive"))
      (node (ref "R36") (pin "2") (pinfunction "2_2") (pintype "passive"))
      (node (ref "U3") (pin "3") (pinfunction "S_3") (pintype "passive"))
      (node (ref "U4") (pin "11") (pinfunction "GND_11") (pintype "passive"))
      (node (ref "U4") (pin "17") (pinfunction "PAD_17") (pintype "passive"))
      (node (ref "U7") (pin "3") (pinfunction "GND_3") (pintype "power_in"))
      (node (ref "U7") (pin "5") (pinfunction "~{ON}/OFF_5") (pintype "input"))
      (node (ref "U8") (pin "1") (pinfunction "GND_1") (pintype "passive"))
    )
    (net (code "46") (name "SGND") (class "Default")
      (node (ref "AO1") (pin "1") (pinfunction "S_1") (pintype "passive"))
      (node (ref "Cx20") (pin "2") (pinfunction "2_2") (pintype "passive"))
      (node (ref "Cx25") (pin "2") (pinfunction "2_2") (pintype "passive"))
      (node (ref "Cx26") (pin "1") (pinfunction "1_1") (pintype "passive"))
      (node (ref "MPP_EN1") (pin "1") (pinfunction "1_1") (pintype "passive"))
      (node (ref "R24") (pin "2") (pinfunction "2_2") (pintype "passive"))
      (node (ref "R25") (pin "2") (pinfunction "2_2") (pintype "passive"))
      (node (ref "R45") (pin "2") (pinfunction "2_2") (pintype "passive"))
      (node (ref "R49") (pin "2") (pinfunction "2_2") (pintype "passive"))
      (node (ref "SGND1") (pin "3") (pinfunction "3_3") (pintype "passive"))
      (node (ref "TERM_EN1") (pin "1") (pinfunction "1_1") (pintype "passive"))
    )
    (net (code "47") (name "unconnected-(SW2A-I{slash}O2-Pad3)") (class "Default")
      (node (ref "SW2") (pin "3") (pinfunction "I/O2_3") (pintype "passive"))
    )
    (net (code "48") (name "unconnected-(SW2B-I{slash}O2-Pad6)") (class "Default")
      (node (ref "SW2") (pin "6") (pinfunction "I/O2_6") (pintype "passive"))
    )
  )
)
